# 1__schdoc.net
KiCad netlist of a schematic drawn in Altium Designer
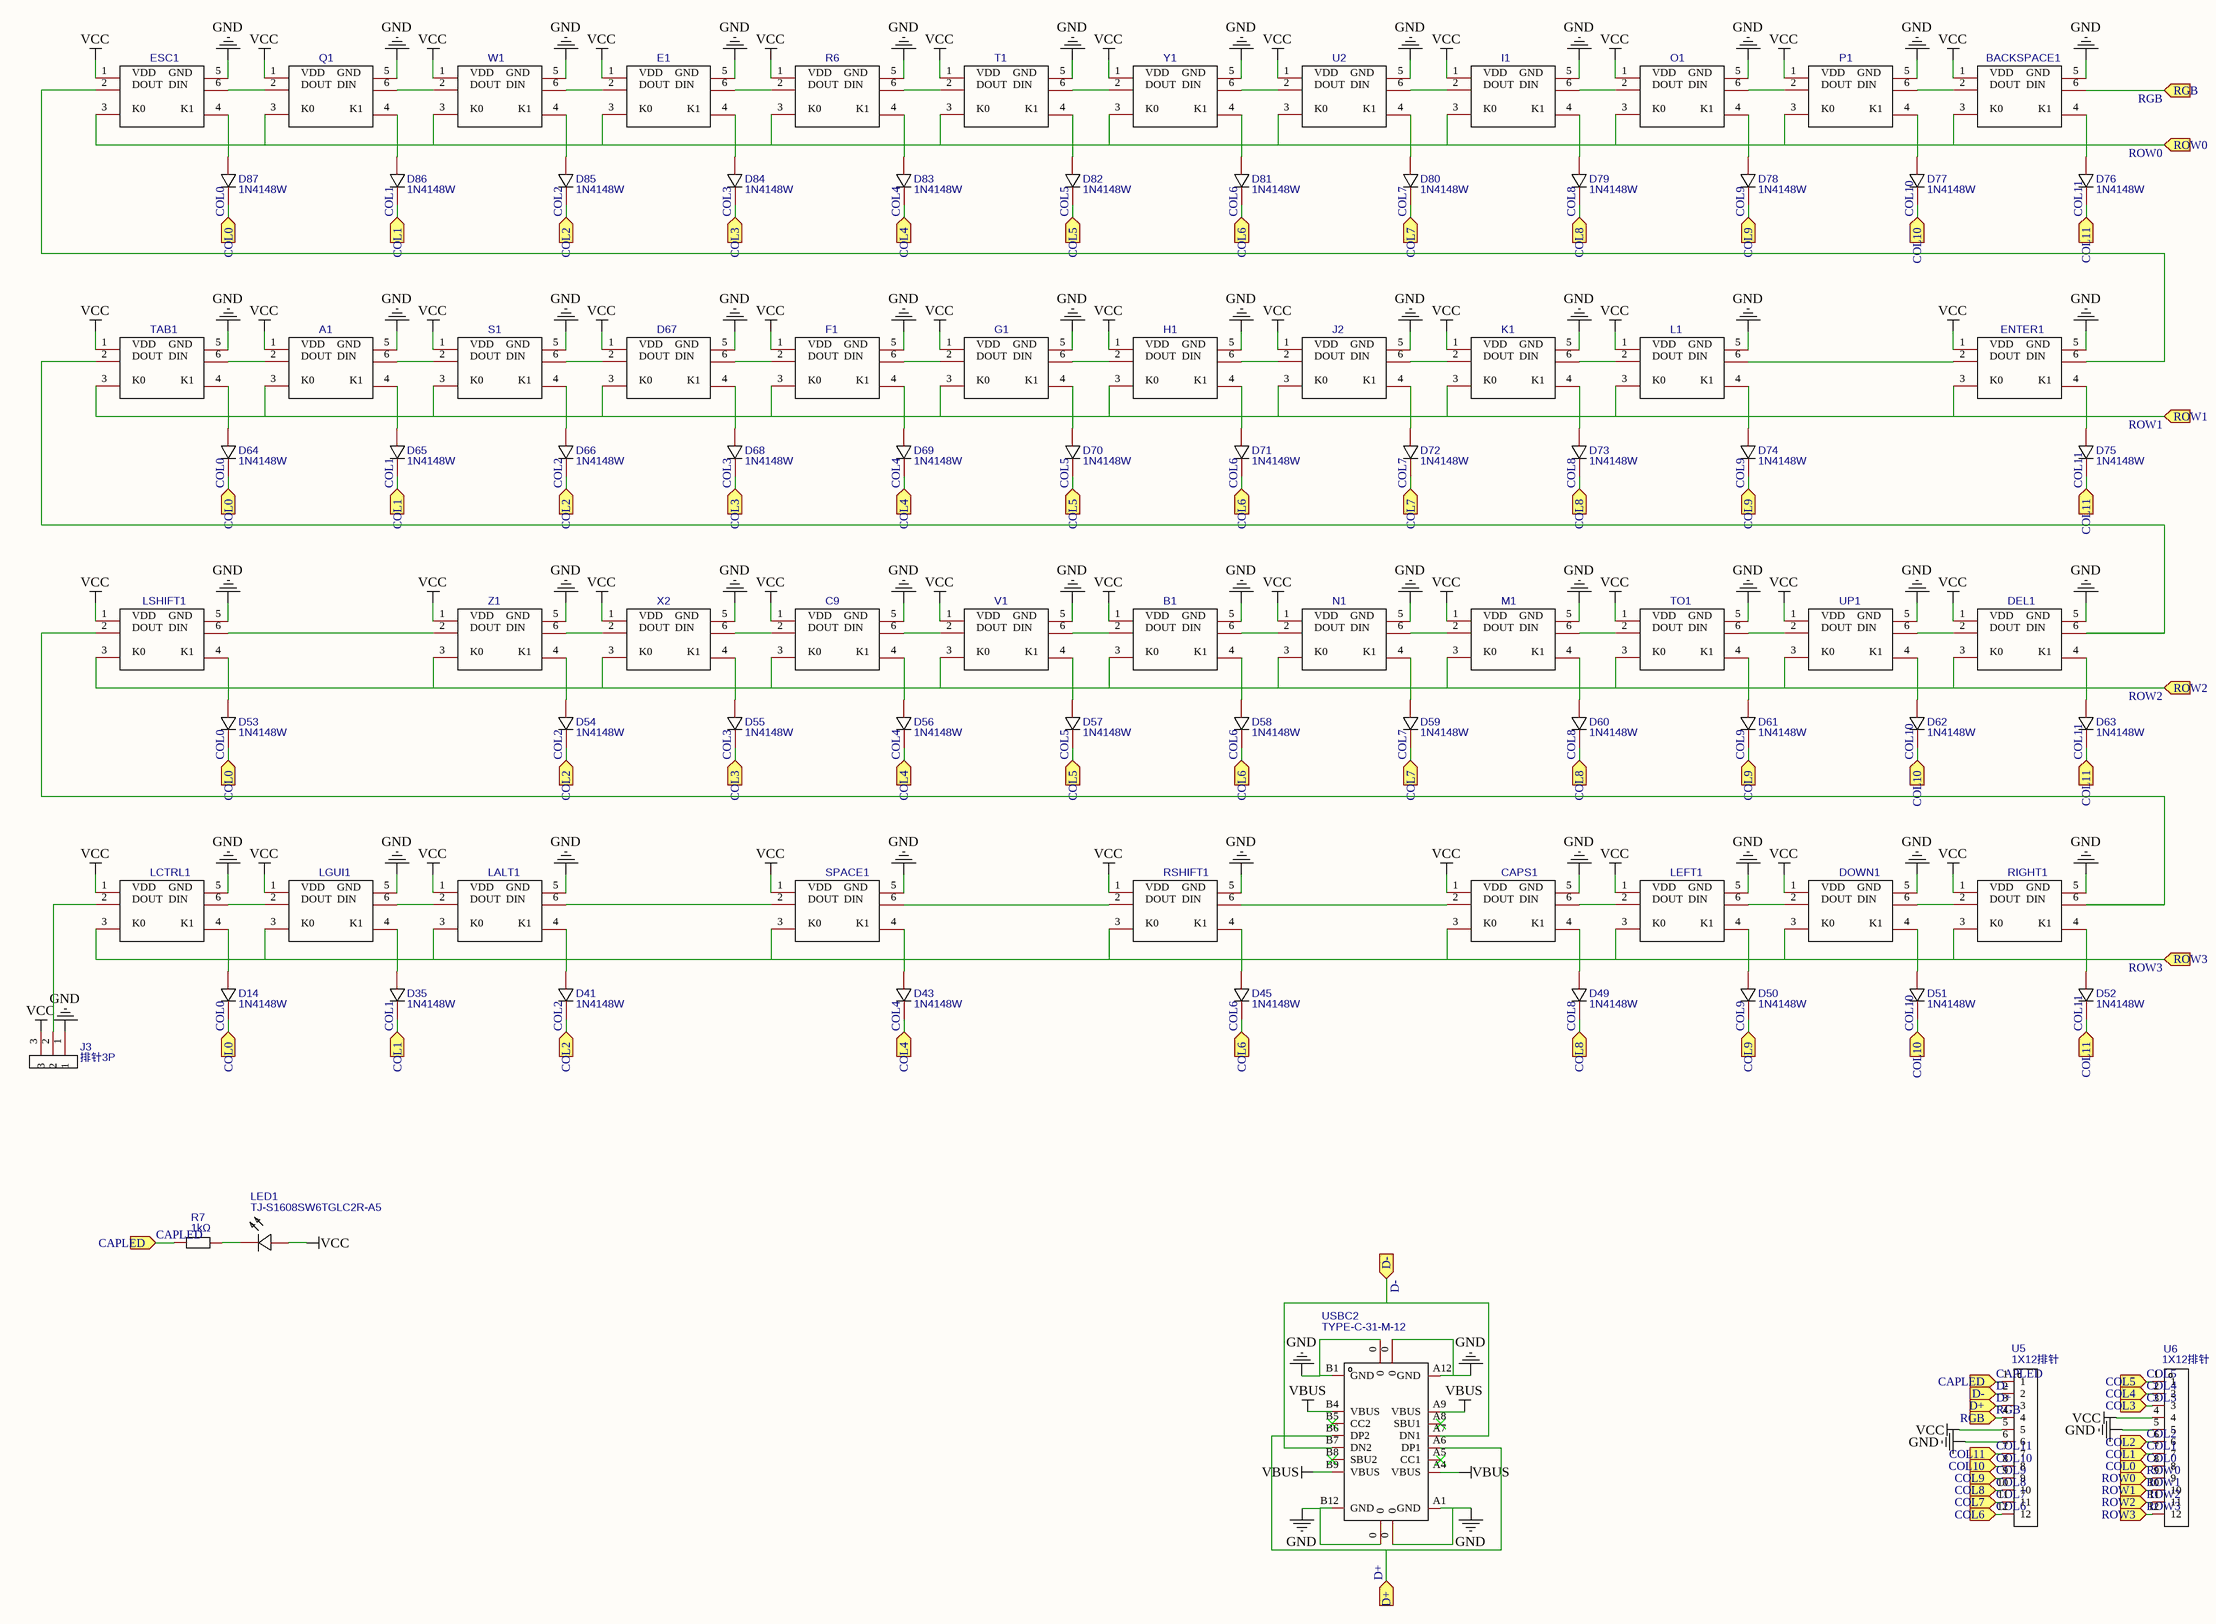
[diagram p0: 1_键盘矩阵.schdoc.schdoc]

(export (version "E")
  (design (tool "Eeschema 10.0.6"))
  (components
    (comp (ref "A1") (value "凯华轴座+3528反贴灯") (libsource (lib "altium-import") (part "root_0_凯华轴座+3528反贴灯_")))
    (comp (ref "B1") (value "凯华轴座+3528反贴灯") (libsource (lib "altium-import") (part "root_0_凯华轴座+3528反贴灯_")))
    (comp (ref "BACKSPACE1")
      (value "凯华轴座+3528反贴灯")
      (libsource (lib "altium-import") (part "root_0_凯华轴座+3528反贴灯_"))
    )
    (comp (ref "C9") (value "凯华轴座+3528反贴灯") (libsource (lib "altium-import") (part "root_0_凯华轴座+3528反贴灯_")))
    (comp (ref "CAPS1")
      (value "凯华轴座+3528反贴灯")
      (libsource (lib "altium-import") (part "root_0_凯华轴座+3528反贴灯_"))
    )
    (comp (ref "D14")
      (value "1N4148W")
      (fields (field (name "NAME") "1N4148W") (field (name "MANUFACTURER") "HT"))
      (libsource (lib "altium-import") (part "root_1_1N4148W_"))
    )
    (comp (ref "D35")
      (value "1N4148W")
      (fields (field (name "NAME") "1N4148W") (field (name "MANUFACTURER") "HT"))
      (libsource (lib "altium-import") (part "root_1_1N4148W_"))
    )
    (comp (ref "D41")
      (value "1N4148W")
      (fields (field (name "NAME") "1N4148W") (field (name "MANUFACTURER") "HT"))
      (libsource (lib "altium-import") (part "root_1_1N4148W_"))
    )
    (comp (ref "D43")
      (value "1N4148W")
      (fields (field (name "NAME") "1N4148W") (field (name "MANUFACTURER") "HT"))
      (libsource (lib "altium-import") (part "root_1_1N4148W_"))
    )
    (comp (ref "D45")
      (value "1N4148W")
      (fields (field (name "NAME") "1N4148W") (field (name "MANUFACTURER") "HT"))
      (libsource (lib "altium-import") (part "root_1_1N4148W_"))
    )
    (comp (ref "D49")
      (value "1N4148W")
      (fields (field (name "NAME") "1N4148W") (field (name "MANUFACTURER") "HT"))
      (libsource (lib "altium-import") (part "root_1_1N4148W_"))
    )
    (comp (ref "D50")
      (value "1N4148W")
      (fields (field (name "NAME") "1N4148W") (field (name "MANUFACTURER") "HT"))
      (libsource (lib "altium-import") (part "root_1_1N4148W_"))
    )
    (comp (ref "D51")
      (value "1N4148W")
      (fields (field (name "NAME") "1N4148W") (field (name "MANUFACTURER") "HT"))
      (libsource (lib "altium-import") (part "root_1_1N4148W_"))
    )
    (comp (ref "D52")
      (value "1N4148W")
      (fields (field (name "NAME") "1N4148W") (field (name "MANUFACTURER") "HT"))
      (libsource (lib "altium-import") (part "root_1_1N4148W_"))
    )
    (comp (ref "D53")
      (value "1N4148W")
      (fields (field (name "NAME") "1N4148W") (field (name "MANUFACTURER") "HT"))
      (libsource (lib "altium-import") (part "root_1_1N4148W_"))
    )
    (comp (ref "D54")
      (value "1N4148W")
      (fields (field (name "NAME") "1N4148W") (field (name "MANUFACTURER") "HT"))
      (libsource (lib "altium-import") (part "root_1_1N4148W_"))
    )
    (comp (ref "D55")
      (value "1N4148W")
      (fields (field (name "NAME") "1N4148W") (field (name "MANUFACTURER") "HT"))
      (libsource (lib "altium-import") (part "root_1_1N4148W_"))
    )
    (comp (ref "D56")
      (value "1N4148W")
      (fields (field (name "NAME") "1N4148W") (field (name "MANUFACTURER") "HT"))
      (libsource (lib "altium-import") (part "root_1_1N4148W_"))
    )
    (comp (ref "D57")
      (value "1N4148W")
      (fields (field (name "NAME") "1N4148W") (field (name "MANUFACTURER") "HT"))
      (libsource (lib "altium-import") (part "root_1_1N4148W_"))
    )
    (comp (ref "D58")
      (value "1N4148W")
      (fields (field (name "NAME") "1N4148W") (field (name "MANUFACTURER") "HT"))
      (libsource (lib "altium-import") (part "root_1_1N4148W_"))
    )
    (comp (ref "D59")
      (value "1N4148W")
      (fields (field (name "NAME") "1N4148W") (field (name "MANUFACTURER") "HT"))
      (libsource (lib "altium-import") (part "root_1_1N4148W_"))
    )
    (comp (ref "D60")
      (value "1N4148W")
      (fields (field (name "NAME") "1N4148W") (field (name "MANUFACTURER") "HT"))
      (libsource (lib "altium-import") (part "root_1_1N4148W_"))
    )
    (comp (ref "D61")
      (value "1N4148W")
      (fields (field (name "NAME") "1N4148W") (field (name "MANUFACTURER") "HT"))
      (libsource (lib "altium-import") (part "root_1_1N4148W_"))
    )
    (comp (ref "D62")
      (value "1N4148W")
      (fields (field (name "NAME") "1N4148W") (field (name "MANUFACTURER") "HT"))
      (libsource (lib "altium-import") (part "root_1_1N4148W_"))
    )
    (comp (ref "D63")
      (value "1N4148W")
      (fields (field (name "NAME") "1N4148W") (field (name "MANUFACTURER") "HT"))
      (libsource (lib "altium-import") (part "root_1_1N4148W_"))
    )
    (comp (ref "D64")
      (value "1N4148W")
      (fields (field (name "NAME") "1N4148W") (field (name "MANUFACTURER") "HT"))
      (libsource (lib "altium-import") (part "root_1_1N4148W_"))
    )
    (comp (ref "D65")
      (value "1N4148W")
      (fields (field (name "NAME") "1N4148W") (field (name "MANUFACTURER") "HT"))
      (libsource (lib "altium-import") (part "root_1_1N4148W_"))
    )
    (comp (ref "D66")
      (value "1N4148W")
      (fields (field (name "NAME") "1N4148W") (field (name "MANUFACTURER") "HT"))
      (libsource (lib "altium-import") (part "root_1_1N4148W_"))
    )
    (comp (ref "D67") (value "凯华轴座+3528反贴灯") (libsource (lib "altium-import") (part "root_0_凯华轴座+3528反贴灯_")))
    (comp (ref "D68")
      (value "1N4148W")
      (fields (field (name "NAME") "1N4148W") (field (name "MANUFACTURER") "HT"))
      (libsource (lib "altium-import") (part "root_1_1N4148W_"))
    )
    (comp (ref "D69")
      (value "1N4148W")
      (fields (field (name "NAME") "1N4148W") (field (name "MANUFACTURER") "HT"))
      (libsource (lib "altium-import") (part "root_1_1N4148W_"))
    )
    (comp (ref "D70")
      (value "1N4148W")
      (fields (field (name "NAME") "1N4148W") (field (name "MANUFACTURER") "HT"))
      (libsource (lib "altium-import") (part "root_1_1N4148W_"))
    )
    (comp (ref "D71")
      (value "1N4148W")
      (fields (field (name "NAME") "1N4148W") (field (name "MANUFACTURER") "HT"))
      (libsource (lib "altium-import") (part "root_1_1N4148W_"))
    )
    (comp (ref "D72")
      (value "1N4148W")
      (fields (field (name "NAME") "1N4148W") (field (name "MANUFACTURER") "HT"))
      (libsource (lib "altium-import") (part "root_1_1N4148W_"))
    )
    (comp (ref "D73")
      (value "1N4148W")
      (fields (field (name "NAME") "1N4148W") (field (name "MANUFACTURER") "HT"))
      (libsource (lib "altium-import") (part "root_1_1N4148W_"))
    )
    (comp (ref "D74")
      (value "1N4148W")
      (fields (field (name "NAME") "1N4148W") (field (name "MANUFACTURER") "HT"))
      (libsource (lib "altium-import") (part "root_1_1N4148W_"))
    )
    (comp (ref "D75")
      (value "1N4148W")
      (fields (field (name "NAME") "1N4148W") (field (name "MANUFACTURER") "HT"))
      (libsource (lib "altium-import") (part "root_1_1N4148W_"))
    )
    (comp (ref "D76")
      (value "1N4148W")
      (fields (field (name "NAME") "1N4148W") (field (name "MANUFACTURER") "HT"))
      (libsource (lib "altium-import") (part "root_1_1N4148W_"))
    )
    (comp (ref "D77")
      (value "1N4148W")
      (fields (field (name "NAME") "1N4148W") (field (name "MANUFACTURER") "HT"))
      (libsource (lib "altium-import") (part "root_1_1N4148W_"))
    )
    (comp (ref "D78")
      (value "1N4148W")
      (fields (field (name "NAME") "1N4148W") (field (name "MANUFACTURER") "HT"))
      (libsource (lib "altium-import") (part "root_1_1N4148W_"))
    )
    (comp (ref "D79")
      (value "1N4148W")
      (fields (field (name "NAME") "1N4148W") (field (name "MANUFACTURER") "HT"))
      (libsource (lib "altium-import") (part "root_1_1N4148W_"))
    )
    (comp (ref "D80")
      (value "1N4148W")
      (fields (field (name "NAME") "1N4148W") (field (name "MANUFACTURER") "HT"))
      (libsource (lib "altium-import") (part "root_1_1N4148W_"))
    )
    (comp (ref "D81")
      (value "1N4148W")
      (fields (field (name "NAME") "1N4148W") (field (name "MANUFACTURER") "HT"))
      (libsource (lib "altium-import") (part "root_1_1N4148W_"))
    )
    (comp (ref "D82")
      (value "1N4148W")
      (fields (field (name "NAME") "1N4148W") (field (name "MANUFACTURER") "HT"))
      (libsource (lib "altium-import") (part "root_1_1N4148W_"))
    )
    (comp (ref "D83")
      (value "1N4148W")
      (fields (field (name "NAME") "1N4148W") (field (name "MANUFACTURER") "HT"))
      (libsource (lib "altium-import") (part "root_1_1N4148W_"))
    )
    (comp (ref "D84")
      (value "1N4148W")
      (fields (field (name "NAME") "1N4148W") (field (name "MANUFACTURER") "HT"))
      (libsource (lib "altium-import") (part "root_1_1N4148W_"))
    )
    (comp (ref "D85")
      (value "1N4148W")
      (fields (field (name "NAME") "1N4148W") (field (name "MANUFACTURER") "HT"))
      (libsource (lib "altium-import") (part "root_1_1N4148W_"))
    )
    (comp (ref "D86")
      (value "1N4148W")
      (fields (field (name "NAME") "1N4148W") (field (name "MANUFACTURER") "HT"))
      (libsource (lib "altium-import") (part "root_1_1N4148W_"))
    )
    (comp (ref "D87")
      (value "1N4148W")
      (fields (field (name "NAME") "1N4148W") (field (name "MANUFACTURER") "HT"))
      (libsource (lib "altium-import") (part "root_1_1N4148W_"))
    )
    (comp (ref "DEL1") (value "凯华轴座+3528反贴灯") (libsource (lib "altium-import") (part "root_0_凯华轴座+3528反贴灯_")))
    (comp (ref "DOWN1")
      (value "凯华轴座+3528反贴灯")
      (libsource (lib "altium-import") (part "root_0_凯华轴座+3528反贴灯_"))
    )
    (comp (ref "E1") (value "凯华轴座+3528反贴灯") (libsource (lib "altium-import") (part "root_0_凯华轴座+3528反贴灯_")))
    (comp (ref "ENTER1")
      (value "凯华轴座+3528反贴灯")
      (libsource (lib "altium-import") (part "root_0_凯华轴座+3528反贴灯_"))
    )
    (comp (ref "ESC1") (value "凯华轴座+3528反贴灯") (libsource (lib "altium-import") (part "root_0_凯华轴座+3528反贴灯_")))
    (comp (ref "F1") (value "凯华轴座+3528反贴灯") (libsource (lib "altium-import") (part "root_0_凯华轴座+3528反贴灯_")))
    (comp (ref "G1") (value "凯华轴座+3528反贴灯") (libsource (lib "altium-import") (part "root_0_凯华轴座+3528反贴灯_")))
    (comp (ref "H1") (value "凯华轴座+3528反贴灯") (libsource (lib "altium-import") (part "root_0_凯华轴座+3528反贴灯_")))
    (comp (ref "I1") (value "凯华轴座+3528反贴灯") (libsource (lib "altium-import") (part "root_0_凯华轴座+3528反贴灯_")))
    (comp (ref "J2") (value "凯华轴座+3528反贴灯") (libsource (lib "altium-import") (part "root_0_凯华轴座+3528反贴灯_")))
    (comp (ref "J3")
      (value "排针3P")
      (fields (field (name "NAME") "排针3P"))
      (libsource (lib "altium-import") (part "root_3_排针3P_"))
    )
    (comp (ref "K1") (value "凯华轴座+3528反贴灯") (libsource (lib "altium-import") (part "root_0_凯华轴座+3528反贴灯_")))
    (comp (ref "L1") (value "凯华轴座+3528反贴灯") (libsource (lib "altium-import") (part "root_0_凯华轴座+3528反贴灯_")))
    (comp (ref "LALT1")
      (value "凯华轴座+3528反贴灯")
      (libsource (lib "altium-import") (part "root_0_凯华轴座+3528反贴灯_"))
    )
    (comp (ref "LCTRL1")
      (value "凯华轴座+3528反贴灯")
      (libsource (lib "altium-import") (part "root_0_凯华轴座+3528反贴灯_"))
    )
    (comp (ref "LED1")
      (value "TJ-S1608SW6TGLC2R-A5")
      (fields (field (name "NAME") "TJ-S1608SW6TGLC2R-A5") (field (name "MANUFACTURER") "TOGIALED"))
      (libsource (lib "altium-import") (part "root_0_TJ-S1608SW6TGLC2R-A5_"))
    )
    (comp (ref "LEFT1")
      (value "凯华轴座+3528反贴灯")
      (libsource (lib "altium-import") (part "root_0_凯华轴座+3528反贴灯_"))
    )
    (comp (ref "LGUI1")
      (value "凯华轴座+3528反贴灯")
      (libsource (lib "altium-import") (part "root_0_凯华轴座+3528反贴灯_"))
    )
    (comp (ref "LSHIFT1")
      (value "凯华轴座+3528反贴灯")
      (libsource (lib "altium-import") (part "root_0_凯华轴座+3528反贴灯_"))
    )
    (comp (ref "M1") (value "凯华轴座+3528反贴灯") (libsource (lib "altium-import") (part "root_0_凯华轴座+3528反贴灯_")))
    (comp (ref "N1") (value "凯华轴座+3528反贴灯") (libsource (lib "altium-import") (part "root_0_凯华轴座+3528反贴灯_")))
    (comp (ref "O1") (value "凯华轴座+3528反贴灯") (libsource (lib "altium-import") (part "root_0_凯华轴座+3528反贴灯_")))
    (comp (ref "P1") (value "凯华轴座+3528反贴灯") (libsource (lib "altium-import") (part "root_0_凯华轴座+3528反贴灯_")))
    (comp (ref "Q1") (value "凯华轴座+3528反贴灯") (libsource (lib "altium-import") (part "root_0_凯华轴座+3528反贴灯_")))
    (comp (ref "R6") (value "凯华轴座+3528反贴灯") (libsource (lib "altium-import") (part "root_0_凯华轴座+3528反贴灯_")))
    (comp (ref "R7")
      (value "1kΩ")
      (fields
        (field (name "NAME") "1kΩ")
        (field (name "MANUFACTURER") "ResistorToday")
        (field (name "MANUFACTURER PART") "ETCR0603F1K00K9")
      )
      (libsource (lib "altium-import") (part "root_0_ETCR0603F1K00K9_"))
    )
    (comp (ref "RIGHT1")
      (value "凯华轴座+3528反贴灯")
      (libsource (lib "altium-import") (part "root_0_凯华轴座+3528反贴灯_"))
    )
    (comp (ref "RSHIFT1")
      (value "凯华轴座+3528反贴灯")
      (libsource (lib "altium-import") (part "root_0_凯华轴座+3528反贴灯_"))
    )
    (comp (ref "S1") (value "凯华轴座+3528反贴灯") (libsource (lib "altium-import") (part "root_0_凯华轴座+3528反贴灯_")))
    (comp (ref "SPACE1")
      (value "凯华轴座+3528反贴灯")
      (libsource (lib "altium-import") (part "root_0_凯华轴座+3528反贴灯_"))
    )
    (comp (ref "T1") (value "凯华轴座+3528反贴灯") (libsource (lib "altium-import") (part "root_0_凯华轴座+3528反贴灯_")))
    (comp (ref "TAB1") (value "凯华轴座+3528反贴灯") (libsource (lib "altium-import") (part "root_0_凯华轴座+3528反贴灯_")))
    (comp (ref "TO1") (value "凯华轴座+3528反贴灯") (libsource (lib "altium-import") (part "root_0_凯华轴座+3528反贴灯_")))
    (comp (ref "U2") (value "凯华轴座+3528反贴灯") (libsource (lib "altium-import") (part "root_0_凯华轴座+3528反贴灯_")))
    (comp (ref "U5")
      (value "1X12排针")
      (fields (field (name "NAME") "1X12排针"))
      (libsource (lib "altium-import") (part "root_0_1X12排针_"))
    )
    (comp (ref "U6")
      (value "1X12排针")
      (fields (field (name "NAME") "1X12排针"))
      (libsource (lib "altium-import") (part "root_0_1X12排针_"))
    )
    (comp (ref "UP1") (value "凯华轴座+3528反贴灯") (libsource (lib "altium-import") (part "root_0_凯华轴座+3528反贴灯_")))
    (comp (ref "USBC2")
      (value "TYPE-C-31-M-12")
      (fields
        (field (name "NAME") "TYPE-C-31-M-12")
        (field (name "MANUFACTURER") "RectangularConnectors-Contacts")
      )
      (libsource (lib "altium-import") (part "root_0_TYPE-C-31-M-12_"))
    )
    (comp (ref "V1") (value "凯华轴座+3528反贴灯") (libsource (lib "altium-import") (part "root_0_凯华轴座+3528反贴灯_")))
    (comp (ref "W1") (value "凯华轴座+3528反贴灯") (libsource (lib "altium-import") (part "root_0_凯华轴座+3528反贴灯_")))
    (comp (ref "X2") (value "凯华轴座+3528反贴灯") (libsource (lib "altium-import") (part "root_0_凯华轴座+3528反贴灯_")))
    (comp (ref "Y1") (value "凯华轴座+3528反贴灯") (libsource (lib "altium-import") (part "root_0_凯华轴座+3528反贴灯_")))
    (comp (ref "Z1") (value "凯华轴座+3528反贴灯") (libsource (lib "altium-import") (part "root_0_凯华轴座+3528反贴灯_")))
  )
  (nets
    (net (code "1") (name "/CAPLED") (class "Default")
      (node (ref "R7") (pin "1") (pinfunction "1_1") (pintype "passive"))
      (node (ref "U5") (pin "1") (pinfunction "1_1") (pintype "passive"))
    )
    (net (code "2") (name "/COL0") (class "Default")
      (node (ref "D14") (pin "1") (pinfunction "K_1") (pintype "passive"))
      (node (ref "D53") (pin "1") (pinfunction "K_1") (pintype "passive"))
      (node (ref "D64") (pin "1") (pinfunction "K_1") (pintype "passive"))
      (node (ref "D87") (pin "1") (pinfunction "K_1") (pintype "passive"))
      (node (ref "U6") (pin "8") (pinfunction "8_8") (pintype "passive"))
    )
    (net (code "3") (name "/COL1") (class "Default")
      (node (ref "D35") (pin "1") (pinfunction "K_1") (pintype "passive"))
      (node (ref "D65") (pin "1") (pinfunction "K_1") (pintype "passive"))
      (node (ref "D86") (pin "1") (pinfunction "K_1") (pintype "passive"))
      (node (ref "U6") (pin "7") (pinfunction "7_7") (pintype "passive"))
    )
    (net (code "4") (name "/COL2") (class "Default")
      (node (ref "D41") (pin "1") (pinfunction "K_1") (pintype "passive"))
      (node (ref "D54") (pin "1") (pinfunction "K_1") (pintype "passive"))
      (node (ref "D66") (pin "1") (pinfunction "K_1") (pintype "passive"))
      (node (ref "D85") (pin "1") (pinfunction "K_1") (pintype "passive"))
      (node (ref "U6") (pin "6") (pinfunction "6_6") (pintype "passive"))
    )
    (net (code "5") (name "/COL3") (class "Default")
      (node (ref "D55") (pin "1") (pinfunction "K_1") (pintype "passive"))
      (node (ref "D68") (pin "1") (pinfunction "K_1") (pintype "passive"))
      (node (ref "D84") (pin "1") (pinfunction "K_1") (pintype "passive"))
      (node (ref "U6") (pin "3") (pinfunction "3_3") (pintype "passive"))
    )
    (net (code "6") (name "/COL4") (class "Default")
      (node (ref "D43") (pin "1") (pinfunction "K_1") (pintype "passive"))
      (node (ref "D56") (pin "1") (pinfunction "K_1") (pintype "passive"))
      (node (ref "D69") (pin "1") (pinfunction "K_1") (pintype "passive"))
      (node (ref "D83") (pin "1") (pinfunction "K_1") (pintype "passive"))
      (node (ref "U6") (pin "2") (pinfunction "2_2") (pintype "passive"))
    )
    (net (code "7") (name "/COL5") (class "Default")
      (node (ref "D57") (pin "1") (pinfunction "K_1") (pintype "passive"))
      (node (ref "D70") (pin "1") (pinfunction "K_1") (pintype "passive"))
      (node (ref "D82") (pin "1") (pinfunction "K_1") (pintype "passive"))
      (node (ref "U6") (pin "1") (pinfunction "1_1") (pintype "passive"))
    )
    (net (code "8") (name "/COL6") (class "Default")
      (node (ref "D45") (pin "1") (pinfunction "K_1") (pintype "passive"))
      (node (ref "D58") (pin "1") (pinfunction "K_1") (pintype "passive"))
      (node (ref "D71") (pin "1") (pinfunction "K_1") (pintype "passive"))
      (node (ref "D81") (pin "1") (pinfunction "K_1") (pintype "passive"))
      (node (ref "U5") (pin "12") (pinfunction "12_12") (pintype "passive"))
    )
    (net (code "9") (name "/COL7") (class "Default")
      (node (ref "D59") (pin "1") (pinfunction "K_1") (pintype "passive"))
      (node (ref "D72") (pin "1") (pinfunction "K_1") (pintype "passive"))
      (node (ref "D80") (pin "1") (pinfunction "K_1") (pintype "passive"))
      (node (ref "U5") (pin "11") (pinfunction "11_11") (pintype "passive"))
    )
    (net (code "10") (name "/COL8") (class "Default")
      (node (ref "D49") (pin "1") (pinfunction "K_1") (pintype "passive"))
      (node (ref "D60") (pin "1") (pinfunction "K_1") (pintype "passive"))
      (node (ref "D73") (pin "1") (pinfunction "K_1") (pintype "passive"))
      (node (ref "D79") (pin "1") (pinfunction "K_1") (pintype "passive"))
      (node (ref "U5") (pin "10") (pinfunction "10_10") (pintype "passive"))
    )
    (net (code "11") (name "/COL9") (class "Default")
      (node (ref "D50") (pin "1") (pinfunction "K_1") (pintype "passive"))
      (node (ref "D61") (pin "1") (pinfunction "K_1") (pintype "passive"))
      (node (ref "D74") (pin "1") (pinfunction "K_1") (pintype "passive"))
      (node (ref "D78") (pin "1") (pinfunction "K_1") (pintype "passive"))
      (node (ref "U5") (pin "9") (pinfunction "9_9") (pintype "passive"))
    )
    (net (code "12") (name "/COL10") (class "Default")
      (node (ref "D51") (pin "1") (pinfunction "K_1") (pintype "passive"))
      (node (ref "D62") (pin "1") (pinfunction "K_1") (pintype "passive"))
      (node (ref "D77") (pin "1") (pinfunction "K_1") (pintype "passive"))
      (node (ref "U5") (pin "8") (pinfunction "8_8") (pintype "passive"))
    )
    (net (code "13") (name "/COL11") (class "Default")
      (node (ref "D52") (pin "1") (pinfunction "K_1") (pintype "passive"))
      (node (ref "D63") (pin "1") (pinfunction "K_1") (pintype "passive"))
      (node (ref "D75") (pin "1") (pinfunction "K_1") (pintype "passive"))
      (node (ref "D76") (pin "1") (pinfunction "K_1") (pintype "passive"))
      (node (ref "U5") (pin "7") (pinfunction "7_7") (pintype "passive"))
    )
    (net (code "14") (name "/D+") (class "Default")
      (node (ref "U5") (pin "3") (pinfunction "3_3") (pintype "passive"))
      (node (ref "USBC2") (pin "A6") (pinfunction "DP1_A6") (pintype "passive"))
      (node (ref "USBC2") (pin "B6") (pinfunction "DP2_B6") (pintype "passive"))
    )
    (net (code "15") (name "/D-") (class "Default")
      (node (ref "U5") (pin "2") (pinfunction "2_2") (pintype "passive"))
      (node (ref "USBC2") (pin "A7") (pinfunction "DN1_A7") (pintype "passive"))
      (node (ref "USBC2") (pin "B7") (pinfunction "DN2_B7") (pintype "passive"))
    )
    (net (code "16") (name "/RGB") (class "Default")
      (node (ref "BACKSPACE1") (pin "6") (pinfunction "6_6") (pintype "passive"))
      (node (ref "U5") (pin "4") (pinfunction "4_4") (pintype "passive"))
    )
    (net (code "17") (name "/ROW0") (class "Default")
      (node (ref "BACKSPACE1") (pin "3") (pinfunction "3_3") (pintype "passive"))
      (node (ref "E1") (pin "3") (pinfunction "3_3") (pintype "passive"))
      (node (ref "ESC1") (pin "3") (pinfunction "3_3") (pintype "passive"))
      (node (ref "I1") (pin "3") (pinfunction "3_3") (pintype "passive"))
      (node (ref "O1") (pin "3") (pinfunction "3_3") (pintype "passive"))
      (node (ref "P1") (pin "3") (pinfunction "3_3") (pintype "passive"))
      (node (ref "Q1") (pin "3") (pinfunction "3_3") (pintype "passive"))
      (node (ref "R6") (pin "3") (pinfunction "3_3") (pintype "passive"))
      (node (ref "T1") (pin "3") (pinfunction "3_3") (pintype "passive"))
      (node (ref "U2") (pin "3") (pinfunction "3_3") (pintype "passive"))
      (node (ref "U6") (pin "9") (pinfunction "9_9") (pintype "passive"))
      (node (ref "W1") (pin "3") (pinfunction "3_3") (pintype "passive"))
      (node (ref "Y1") (pin "3") (pinfunction "3_3") (pintype "passive"))
    )
    (net (code "18") (name "/ROW1") (class "Default")
      (node (ref "A1") (pin "3") (pinfunction "3_3") (pintype "passive"))
      (node (ref "D67") (pin "3") (pinfunction "3_3") (pintype "passive"))
      (node (ref "ENTER1") (pin "3") (pinfunction "3_3") (pintype "passive"))
      (node (ref "F1") (pin "3") (pinfunction "3_3") (pintype "passive"))
      (node (ref "G1") (pin "3") (pinfunction "3_3") (pintype "passive"))
      (node (ref "H1") (pin "3") (pinfunction "3_3") (pintype "passive"))
      (node (ref "J2") (pin "3") (pinfunction "3_3") (pintype "passive"))
      (node (ref "K1") (pin "3") (pinfunction "3_3") (pintype "passive"))
      (node (ref "L1") (pin "3") (pinfunction "3_3") (pintype "passive"))
      (node (ref "S1") (pin "3") (pinfunction "3_3") (pintype "passive"))
      (node (ref "TAB1") (pin "3") (pinfunction "3_3") (pintype "passive"))
      (node (ref "U6") (pin "10") (pinfunction "10_10") (pintype "passive"))
    )
    (net (code "19") (name "/ROW2") (class "Default")
      (node (ref "B1") (pin "3") (pinfunction "3_3") (pintype "passive"))
      (node (ref "C9") (pin "3") (pinfunction "3_3") (pintype "passive"))
      (node (ref "DEL1") (pin "3") (pinfunction "3_3") (pintype "passive"))
      (node (ref "LSHIFT1") (pin "3") (pinfunction "3_3") (pintype "passive"))
      (node (ref "M1") (pin "3") (pinfunction "3_3") (pintype "passive"))
      (node (ref "N1") (pin "3") (pinfunction "3_3") (pintype "passive"))
      (node (ref "TO1") (pin "3") (pinfunction "3_3") (pintype "passive"))
      (node (ref "U6") (pin "11") (pinfunction "11_11") (pintype "passive"))
      (node (ref "UP1") (pin "3") (pinfunction "3_3") (pintype "passive"))
      (node (ref "V1") (pin "3") (pinfunction "3_3") (pintype "passive"))
      (node (ref "X2") (pin "3") (pinfunction "3_3") (pintype "passive"))
      (node (ref "Z1") (pin "3") (pinfunction "3_3") (pintype "passive"))
    )
    (net (code "20") (name "/ROW3") (class "Default")
      (node (ref "CAPS1") (pin "3") (pinfunction "3_3") (pintype "passive"))
      (node (ref "DOWN1") (pin "3") (pinfunction "3_3") (pintype "passive"))
      (node (ref "LALT1") (pin "3") (pinfunction "3_3") (pintype "passive"))
      (node (ref "LCTRL1") (pin "3") (pinfunction "3_3") (pintype "passive"))
      (node (ref "LEFT1") (pin "3") (pinfunction "3_3") (pintype "passive"))
      (node (ref "LGUI1") (pin "3") (pinfunction "3_3") (pintype "passive"))
      (node (ref "RIGHT1") (pin "3") (pinfunction "3_3") (pintype "passive"))
      (node (ref "RSHIFT1") (pin "3") (pinfunction "3_3") (pintype "passive"))
      (node (ref "SPACE1") (pin "3") (pinfunction "3_3") (pintype "passive"))
      (node (ref "U6") (pin "12") (pinfunction "12_12") (pintype "passive"))
    )
    (net (code "21") (name "GND") (class "Default")
      (node (ref "A1") (pin "5") (pinfunction "5_5") (pintype "passive"))
      (node (ref "B1") (pin "5") (pinfunction "5_5") (pintype "passive"))
      (node (ref "BACKSPACE1") (pin "5") (pinfunction "5_5") (pintype "passive"))
      (node (ref "C9") (pin "5") (pinfunction "5_5") (pintype "passive"))
      (node (ref "CAPS1") (pin "5") (pinfunction "5_5") (pintype "passive"))
      (node (ref "D67") (pin "5") (pinfunction "5_5") (pintype "passive"))
      (node (ref "DEL1") (pin "5") (pinfunction "5_5") (pintype "passive"))
      (node (ref "DOWN1") (pin "5") (pinfunction "5_5") (pintype "passive"))
      (node (ref "E1") (pin "5") (pinfunction "5_5") (pintype "passive"))
      (node (ref "ENTER1") (pin "5") (pinfunction "5_5") (pintype "passive"))
      (node (ref "ESC1") (pin "5") (pinfunction "5_5") (pintype "passive"))
      (node (ref "F1") (pin "5") (pinfunction "5_5") (pintype "passive"))
      (node (ref "G1") (pin "5") (pinfunction "5_5") (pintype "passive"))
      (node (ref "H1") (pin "5") (pinfunction "5_5") (pintype "passive"))
      (node (ref "I1") (pin "5") (pinfunction "5_5") (pintype "passive"))
      (node (ref "J2") (pin "5") (pinfunction "5_5") (pintype "passive"))
      (node (ref "J3") (pin "1") (pinfunction "1_1") (pintype "passive"))
      (node (ref "K1") (pin "5") (pinfunction "5_5") (pintype "passive"))
      (node (ref "L1") (pin "5") (pinfunction "5_5") (pintype "passive"))
      (node (ref "LALT1") (pin "5") (pinfunction "5_5") (pintype "passive"))
      (node (ref "LCTRL1") (pin "5") (pinfunction "5_5") (pintype "passive"))
      (node (ref "LEFT1") (pin "5") (pinfunction "5_5") (pintype "passive"))
      (node (ref "LGUI1") (pin "5") (pinfunction "5_5") (pintype "passive"))
      (node (ref "LSHIFT1") (pin "5") (pinfunction "5_5") (pintype "passive"))
      (node (ref "M1") (pin "5") (pinfunction "5_5") (pintype "passive"))
      (node (ref "N1") (pin "5") (pinfunction "5_5") (pintype "passive"))
      (node (ref "O1") (pin "5") (pinfunction "5_5") (pintype "passive"))
      (node (ref "P1") (pin "5") (pinfunction "5_5") (pintype "passive"))
      (node (ref "Q1") (pin "5") (pinfunction "5_5") (pintype "passive"))
      (node (ref "R6") (pin "5") (pinfunction "5_5") (pintype "passive"))
      (node (ref "RIGHT1") (pin "5") (pinfunction "5_5") (pintype "passive"))
      (node (ref "RSHIFT1") (pin "5") (pinfunction "5_5") (pintype "passive"))
      (node (ref "S1") (pin "5") (pinfunction "5_5") (pintype "passive"))
      (node (ref "SPACE1") (pin "5") (pinfunction "5_5") (pintype "passive"))
      (node (ref "T1") (pin "5") (pinfunction "5_5") (pintype "passive"))
      (node (ref "TAB1") (pin "5") (pinfunction "5_5") (pintype "passive"))
      (node (ref "TO1") (pin "5") (pinfunction "5_5") (pintype "passive"))
      (node (ref "U2") (pin "5") (pinfunction "5_5") (pintype "passive"))
      (node (ref "U5") (pin "6") (pinfunction "6_6") (pintype "passive"))
      (node (ref "U6") (pin "5") (pinfunction "5_5") (pintype "passive"))
      (node (ref "UP1") (pin "5") (pinfunction "5_5") (pintype "passive"))
      (node (ref "USBC2") (pin "0") (pinfunction "0_0") (pintype "passive"))
      (node (ref "USBC2") (pin "A1") (pinfunction "GND_A1") (pintype "passive"))
      (node (ref "USBC2") (pin "A12") (pinfunction "GND_A12") (pintype "passive"))
      (node (ref "USBC2") (pin "B1") (pinfunction "GND_B1") (pintype "passive"))
      (node (ref "USBC2") (pin "B12") (pinfunction "GND_B12") (pintype "passive"))
      (node (ref "V1") (pin "5") (pinfunction "5_5") (pintype "passive"))
      (node (ref "W1") (pin "5") (pinfunction "5_5") (pintype "passive"))
      (node (ref "X2") (pin "5") (pinfunction "5_5") (pintype "passive"))
      (node (ref "Y1") (pin "5") (pinfunction "5_5") (pintype "passive"))
      (node (ref "Z1") (pin "5") (pinfunction "5_5") (pintype "passive"))
    )
    (net (code "22") (name "Net-(A1-Pad2)") (class "Default")
      (node (ref "A1") (pin "2") (pinfunction "2_2") (pintype "passive"))
      (node (ref "TAB1") (pin "6") (pinfunction "6_6") (pintype "passive"))
    )
    (net (code "23") (name "Net-(A1-Pad6)") (class "Default")
      (node (ref "A1") (pin "6") (pinfunction "6_6") (pintype "passive"))
      (node (ref "S1") (pin "2") (pinfunction "2_2") (pintype "passive"))
    )
    (net (code "24") (name "Net-(B1-Pad2)") (class "Default")
      (node (ref "B1") (pin "2") (pinfunction "2_2") (pintype "passive"))
      (node (ref "V1") (pin "6") (pinfunction "6_6") (pintype "passive"))
    )
    (net (code "25") (name "Net-(B1-Pad6)") (class "Default")
      (node (ref "B1") (pin "6") (pinfunction "6_6") (pintype "passive"))
      (node (ref "N1") (pin "2") (pinfunction "2_2") (pintype "passive"))
    )
    (net (code "26") (name "Net-(BACKSPACE1-Pad2)") (class "Default")
      (node (ref "BACKSPACE1") (pin "2") (pinfunction "2_2") (pintype "passive"))
      (node (ref "P1") (pin "6") (pinfunction "6_6") (pintype "passive"))
    )
    (net (code "27") (name "Net-(C9-Pad2)") (class "Default")
      (node (ref "C9") (pin "2") (pinfunction "2_2") (pintype "passive"))
      (node (ref "X2") (pin "6") (pinfunction "6_6") (pintype "passive"))
    )
    (net (code "28") (name "Net-(C9-Pad6)") (class "Default")
      (node (ref "C9") (pin "6") (pinfunction "6_6") (pintype "passive"))
      (node (ref "V1") (pin "2") (pinfunction "2_2") (pintype "passive"))
    )
    (net (code "29") (name "Net-(CAPS1-Pad2)") (class "Default")
      (node (ref "CAPS1") (pin "2") (pinfunction "2_2") (pintype "passive"))
      (node (ref "RSHIFT1") (pin "6") (pinfunction "6_6") (pintype "passive"))
    )
    (net (code "30") (name "Net-(CAPS1-Pad6)") (class "Default")
      (node (ref "CAPS1") (pin "6") (pinfunction "6_6") (pintype "passive"))
      (node (ref "LEFT1") (pin "2") (pinfunction "2_2") (pintype "passive"))
    )
    (net (code "31") (name "Net-(D14-A)") (class "Default")
      (node (ref "D14") (pin "2") (pinfunction "A_2") (pintype "passive"))
      (node (ref "LCTRL1") (pin "4") (pinfunction "4_4") (pintype "passive"))
    )
    (net (code "32") (name "Net-(D35-A)") (class "Default")
      (node (ref "D35") (pin "2") (pinfunction "A_2") (pintype "passive"))
      (node (ref "LGUI1") (pin "4") (pinfunction "4_4") (pintype "passive"))
    )
    (net (code "33") (name "Net-(D41-A)") (class "Default")
      (node (ref "D41") (pin "2") (pinfunction "A_2") (pintype "passive"))
      (node (ref "LALT1") (pin "4") (pinfunction "4_4") (pintype "passive"))
    )
    (net (code "34") (name "Net-(D43-A)") (class "Default")
      (node (ref "D43") (pin "2") (pinfunction "A_2") (pintype "passive"))
      (node (ref "SPACE1") (pin "4") (pinfunction "4_4") (pintype "passive"))
    )
    (net (code "35") (name "Net-(D45-A)") (class "Default")
      (node (ref "D45") (pin "2") (pinfunction "A_2") (pintype "passive"))
      (node (ref "RSHIFT1") (pin "4") (pinfunction "4_4") (pintype "passive"))
    )
    (net (code "36") (name "Net-(D49-A)") (class "Default")
      (node (ref "CAPS1") (pin "4") (pinfunction "4_4") (pintype "passive"))
      (node (ref "D49") (pin "2") (pinfunction "A_2") (pintype "passive"))
    )
    (net (code "37") (name "Net-(D50-A)") (class "Default")
      (node (ref "D50") (pin "2") (pinfunction "A_2") (pintype "passive"))
      (node (ref "LEFT1") (pin "4") (pinfunction "4_4") (pintype "passive"))
    )
    (net (code "38") (name "Net-(D51-A)") (class "Default")
      (node (ref "D51") (pin "2") (pinfunction "A_2") (pintype "passive"))
      (node (ref "DOWN1") (pin "4") (pinfunction "4_4") (pintype "passive"))
    )
    (net (code "39") (name "Net-(D52-A)") (class "Default")
      (node (ref "D52") (pin "2") (pinfunction "A_2") (pintype "passive"))
      (node (ref "RIGHT1") (pin "4") (pinfunction "4_4") (pintype "passive"))
    )
    (net (code "40") (name "Net-(D53-A)") (class "Default")
      (node (ref "D53") (pin "2") (pinfunction "A_2") (pintype "passive"))
      (node (ref "LSHIFT1") (pin "4") (pinfunction "4_4") (pintype "passive"))
    )
    (net (code "41") (name "Net-(D54-A)") (class "Default")
      (node (ref "D54") (pin "2") (pinfunction "A_2") (pintype "passive"))
      (node (ref "Z1") (pin "4") (pinfunction "4_4") (pintype "passive"))
    )
    (net (code "42") (name "Net-(D55-A)") (class "Default")
      (node (ref "D55") (pin "2") (pinfunction "A_2") (pintype "passive"))
      (node (ref "X2") (pin "4") (pinfunction "4_4") (pintype "passive"))
    )
    (net (code "43") (name "Net-(D56-A)") (class "Default")
      (node (ref "C9") (pin "4") (pinfunction "4_4") (pintype "passive"))
      (node (ref "D56") (pin "2") (pinfunction "A_2") (pintype "passive"))
    )
    (net (code "44") (name "Net-(D57-A)") (class "Default")
      (node (ref "D57") (pin "2") (pinfunction "A_2") (pintype "passive"))
      (node (ref "V1") (pin "4") (pinfunction "4_4") (pintype "passive"))
    )
    (net (code "45") (name "Net-(D58-A)") (class "Default")
      (node (ref "B1") (pin "4") (pinfunction "4_4") (pintype "passive"))
      (node (ref "D58") (pin "2") (pinfunction "A_2") (pintype "passive"))
    )
    (net (code "46") (name "Net-(D59-A)") (class "Default")
      (node (ref "D59") (pin "2") (pinfunction "A_2") (pintype "passive"))
      (node (ref "N1") (pin "4") (pinfunction "4_4") (pintype "passive"))
    )
    (net (code "47") (name "Net-(D60-A)") (class "Default")
      (node (ref "D60") (pin "2") (pinfunction "A_2") (pintype "passive"))
      (node (ref "M1") (pin "4") (pinfunction "4_4") (pintype "passive"))
    )
    (net (code "48") (name "Net-(D61-A)") (class "Default")
      (node (ref "D61") (pin "2") (pinfunction "A_2") (pintype "passive"))
      (node (ref "TO1") (pin "4") (pinfunction "4_4") (pintype "passive"))
    )
    (net (code "49") (name "Net-(D62-A)") (class "Default")
      (node (ref "D62") (pin "2") (pinfunction "A_2") (pintype "passive"))
      (node (ref "UP1") (pin "4") (pinfunction "4_4") (pintype "passive"))
    )
    (net (code "50") (name "Net-(D63-A)") (class "Default")
      (node (ref "D63") (pin "2") (pinfunction "A_2") (pintype "passive"))
      (node (ref "DEL1") (pin "4") (pinfunction "4_4") (pintype "passive"))
    )
    (net (code "51") (name "Net-(D64-A)") (class "Default")
      (node (ref "D64") (pin "2") (pinfunction "A_2") (pintype "passive"))
      (node (ref "TAB1") (pin "4") (pinfunction "4_4") (pintype "passive"))
    )
    (net (code "52") (name "Net-(D65-A)") (class "Default")
      (node (ref "A1") (pin "4") (pinfunction "4_4") (pintype "passive"))
      (node (ref "D65") (pin "2") (pinfunction "A_2") (pintype "passive"))
    )
    (net (code "53") (name "Net-(D66-A)") (class "Default")
      (node (ref "D66") (pin "2") (pinfunction "A_2") (pintype "passive"))
      (node (ref "S1") (pin "4") (pinfunction "4_4") (pintype "passive"))
    )
    (net (code "54") (name "Net-(D67-Pad2)") (class "Default")
      (node (ref "D67") (pin "2") (pinfunction "2_2") (pintype "passive"))
      (node (ref "S1") (pin "6") (pinfunction "6_6") (pintype "passive"))
    )
    (net (code "55") (name "Net-(D67-Pad6)") (class "Default")
      (node (ref "D67") (pin "6") (pinfunction "6_6") (pintype "passive"))
      (node (ref "F1") (pin "2") (pinfunction "2_2") (pintype "passive"))
    )
    (net (code "56") (name "Net-(D68-A)") (class "Default")
      (node (ref "D67") (pin "4") (pinfunction "4_4") (pintype "passive"))
      (node (ref "D68") (pin "2") (pinfunction "A_2") (pintype "passive"))
    )
    (net (code "57") (name "Net-(D69-A)") (class "Default")
      (node (ref "D69") (pin "2") (pinfunction "A_2") (pintype "passive"))
      (node (ref "F1") (pin "4") (pinfunction "4_4") (pintype "passive"))
    )
    (net (code "58") (name "Net-(D70-A)") (class "Default")
      (node (ref "D70") (pin "2") (pinfunction "A_2") (pintype "passive"))
      (node (ref "G1") (pin "4") (pinfunction "4_4") (pintype "passive"))
    )
    (net (code "59") (name "Net-(D71-A)") (class "Default")
      (node (ref "D71") (pin "2") (pinfunction "A_2") (pintype "passive"))
      (node (ref "H1") (pin "4") (pinfunction "4_4") (pintype "passive"))
    )
    (net (code "60") (name "Net-(D72-A)") (class "Default")
      (node (ref "D72") (pin "2") (pinfunction "A_2") (pintype "passive"))
      (node (ref "J2") (pin "4") (pinfunction "4_4") (pintype "passive"))
    )
    (net (code "61") (name "Net-(D73-A)") (class "Default")
      (node (ref "D73") (pin "2") (pinfunction "A_2") (pintype "passive"))
      (node (ref "K1") (pin "4") (pinfunction "4_4") (pintype "passive"))
    )
    (net (code "62") (name "Net-(D74-A)") (class "Default")
      (node (ref "D74") (pin "2") (pinfunction "A_2") (pintype "passive"))
      (node (ref "L1") (pin "4") (pinfunction "4_4") (pintype "passive"))
    )
    (net (code "63") (name "Net-(D75-A)") (class "Default")
      (node (ref "D75") (pin "2") (pinfunction "A_2") (pintype "passive"))
      (node (ref "ENTER1") (pin "4") (pinfunction "4_4") (pintype "passive"))
    )
    (net (code "64") (name "Net-(D76-A)") (class "Default")
      (node (ref "BACKSPACE1") (pin "4") (pinfunction "4_4") (pintype "passive"))
      (node (ref "D76") (pin "2") (pinfunction "A_2") (pintype "passive"))
    )
    (net (code "65") (name "Net-(D77-A)") (class "Default")
      (node (ref "D77") (pin "2") (pinfunction "A_2") (pintype "passive"))
      (node (ref "P1") (pin "4") (pinfunction "4_4") (pintype "passive"))
    )
    (net (code "66") (name "Net-(D78-A)") (class "Default")
      (node (ref "D78") (pin "2") (pinfunction "A_2") (pintype "passive"))
      (node (ref "O1") (pin "4") (pinfunction "4_4") (pintype "passive"))
    )
    (net (code "67") (name "Net-(D79-A)") (class "Default")
      (node (ref "D79") (pin "2") (pinfunction "A_2") (pintype "passive"))
      (node (ref "I1") (pin "4") (pinfunction "4_4") (pintype "passive"))
    )
    (net (code "68") (name "Net-(D80-A)") (class "Default")
      (node (ref "D80") (pin "2") (pinfunction "A_2") (pintype "passive"))
      (node (ref "U2") (pin "4") (pinfunction "4_4") (pintype "passive"))
    )
    (net (code "69") (name "Net-(D81-A)") (class "Default")
      (node (ref "D81") (pin "2") (pinfunction "A_2") (pintype "passive"))
      (node (ref "Y1") (pin "4") (pinfunction "4_4") (pintype "passive"))
    )
    (net (code "70") (name "Net-(D82-A)") (class "Default")
      (node (ref "D82") (pin "2") (pinfunction "A_2") (pintype "passive"))
      (node (ref "T1") (pin "4") (pinfunction "4_4") (pintype "passive"))
    )
    (net (code "71") (name "Net-(D83-A)") (class "Default")
      (node (ref "D83") (pin "2") (pinfunction "A_2") (pintype "passive"))
      (node (ref "R6") (pin "4") (pinfunction "4_4") (pintype "passive"))
    )
    (net (code "72") (name "Net-(D84-A)") (class "Default")
      (node (ref "D84") (pin "2") (pinfunction "A_2") (pintype "passive"))
      (node (ref "E1") (pin "4") (pinfunction "4_4") (pintype "passive"))
    )
    (net (code "73") (name "Net-(D85-A)") (class "Default")
      (node (ref "D85") (pin "2") (pinfunction "A_2") (pintype "passive"))
      (node (ref "W1") (pin "4") (pinfunction "4_4") (pintype "passive"))
    )
    (net (code "74") (name "Net-(D86-A)") (class "Default")
      (node (ref "D86") (pin "2") (pinfunction "A_2") (pintype "passive"))
      (node (ref "Q1") (pin "4") (pinfunction "4_4") (pintype "passive"))
    )
    (net (code "75") (name "Net-(D87-A)") (class "Default")
      (node (ref "D87") (pin "2") (pinfunction "A_2") (pintype "passive"))
      (node (ref "ESC1") (pin "4") (pinfunction "4_4") (pintype "passive"))
    )
    (net (code "76") (name "Net-(DEL1-Pad2)") (class "Default")
      (node (ref "DEL1") (pin "2") (pinfunction "2_2") (pintype "passive"))
      (node (ref "UP1") (pin "6") (pinfunction "6_6") (pintype "passive"))
    )
    (net (code "77") (name "Net-(DEL1-Pad6)") (class "Default")
      (node (ref "DEL1") (pin "6") (pinfunction "6_6") (pintype "passive"))
      (node (ref "TAB1") (pin "2") (pinfunction "2_2") (pintype "passive"))
    )
    (net (code "78") (name "Net-(DOWN1-Pad2)") (class "Default")
      (node (ref "DOWN1") (pin "2") (pinfunction "2_2") (pintype "passive"))
      (node (ref "LEFT1") (pin "6") (pinfunction "6_6") (pintype "passive"))
    )
    (net (code "79") (name "Net-(DOWN1-Pad6)") (class "Default")
      (node (ref "DOWN1") (pin "6") (pinfunction "6_6") (pintype "passive"))
      (node (ref "RIGHT1") (pin "2") (pinfunction "2_2") (pintype "passive"))
    )
    (net (code "80") (name "Net-(E1-Pad2)") (class "Default")
      (node (ref "E1") (pin "2") (pinfunction "2_2") (pintype "passive"))
      (node (ref "W1") (pin "6") (pinfunction "6_6") (pintype "passive"))
    )
    (net (code "81") (name "Net-(E1-Pad6)") (class "Default")
      (node (ref "E1") (pin "6") (pinfunction "6_6") (pintype "passive"))
      (node (ref "R6") (pin "2") (pinfunction "2_2") (pintype "passive"))
    )
    (net (code "82") (name "Net-(ENTER1-Pad2)") (class "Default")
      (node (ref "ENTER1") (pin "2") (pinfunction "2_2") (pintype "passive"))
      (node (ref "L1") (pin "6") (pinfunction "6_6") (pintype "passive"))
    )
    (net (code "83") (name "Net-(ENTER1-Pad6)") (class "Default")
      (node (ref "ENTER1") (pin "6") (pinfunction "6_6") (pintype "passive"))
      (node (ref "ESC1") (pin "2") (pinfunction "2_2") (pintype "passive"))
    )
    (net (code "84") (name "Net-(ESC1-Pad6)") (class "Default")
      (node (ref "ESC1") (pin "6") (pinfunction "6_6") (pintype "passive"))
      (node (ref "Q1") (pin "2") (pinfunction "2_2") (pintype "passive"))
    )
    (net (code "85") (name "Net-(F1-Pad6)") (class "Default")
      (node (ref "F1") (pin "6") (pinfunction "6_6") (pintype "passive"))
      (node (ref "G1") (pin "2") (pinfunction "2_2") (pintype "passive"))
    )
    (net (code "86") (name "Net-(G1-Pad6)") (class "Default")
      (node (ref "G1") (pin "6") (pinfunction "6_6") (pintype "passive"))
      (node (ref "H1") (pin "2") (pinfunction "2_2") (pintype "passive"))
    )
    (net (code "87") (name "Net-(H1-Pad6)") (class "Default")
      (node (ref "H1") (pin "6") (pinfunction "6_6") (pintype "passive"))
      (node (ref "J2") (pin "2") (pinfunction "2_2") (pintype "passive"))
    )
    (net (code "88") (name "Net-(I1-Pad2)") (class "Default")
      (node (ref "I1") (pin "2") (pinfunction "2_2") (pintype "passive"))
      (node (ref "U2") (pin "6") (pinfunction "6_6") (pintype "passive"))
    )
    (net (code "89") (name "Net-(I1-Pad6)") (class "Default")
      (node (ref "I1") (pin "6") (pinfunction "6_6") (pintype "passive"))
      (node (ref "O1") (pin "2") (pinfunction "2_2") (pintype "passive"))
    )
    (net (code "90") (name "Net-(J2-Pad6)") (class "Default")
      (node (ref "J2") (pin "6") (pinfunction "6_6") (pintype "passive"))
      (node (ref "K1") (pin "2") (pinfunction "2_2") (pintype "passive"))
    )
    (net (code "91") (name "Net-(J3-Pad2)") (class "Default")
      (node (ref "J3") (pin "2") (pinfunction "2_2") (pintype "passive"))
      (node (ref "LCTRL1") (pin "2") (pinfunction "2_2") (pintype "passive"))
    )
    (net (code "92") (name "Net-(K1-Pad6)") (class "Default")
      (node (ref "K1") (pin "6") (pinfunction "6_6") (pintype "passive"))
      (node (ref "L1") (pin "2") (pinfunction "2_2") (pintype "passive"))
    )
    (net (code "93") (name "Net-(LALT1-Pad2)") (class "Default")
      (node (ref "LALT1") (pin "2") (pinfunction "2_2") (pintype "passive"))
      (node (ref "LGUI1") (pin "6") (pinfunction "6_6") (pintype "passive"))
    )
    (net (code "94") (name "Net-(LALT1-Pad6)") (class "Default")
      (node (ref "LALT1") (pin "6") (pinfunction "6_6") (pintype "passive"))
      (node (ref "SPACE1") (pin "2") (pinfunction "2_2") (pintype "passive"))
    )
    (net (code "95") (name "Net-(LCTRL1-Pad6)") (class "Default")
      (node (ref "LCTRL1") (pin "6") (pinfunction "6_6") (pintype "passive"))
      (node (ref "LGUI1") (pin "2") (pinfunction "2_2") (pintype "passive"))
    )
    (net (code "96") (name "Net-(LED1-K)") (class "Default")
      (node (ref "LED1") (pin "2") (pinfunction "K_2") (pintype "passive"))
      (node (ref "R7") (pin "2") (pinfunction "2_2") (pintype "passive"))
    )
    (net (code "97") (name "Net-(LSHIFT1-Pad2)") (class "Default")
      (node (ref "LSHIFT1") (pin "2") (pinfunction "2_2") (pintype "passive"))
      (node (ref "RIGHT1") (pin "6") (pinfunction "6_6") (pintype "passive"))
    )
    (net (code "98") (name "Net-(LSHIFT1-Pad6)") (class "Default")
      (node (ref "LSHIFT1") (pin "6") (pinfunction "6_6") (pintype "passive"))
      (node (ref "Z1") (pin "2") (pinfunction "2_2") (pintype "passive"))
    )
    (net (code "99") (name "Net-(M1-Pad2)") (class "Default")
      (node (ref "M1") (pin "2") (pinfunction "2_2") (pintype "passive"))
      (node (ref "N1") (pin "6") (pinfunction "6_6") (pintype "passive"))
    )
    (net (code "100") (name "Net-(M1-Pad6)") (class "Default")
      (node (ref "M1") (pin "6") (pinfunction "6_6") (pintype "passive"))
      (node (ref "TO1") (pin "2") (pinfunction "2_2") (pintype "passive"))
    )
    (net (code "101") (name "Net-(O1-Pad6)") (class "Default")
      (node (ref "O1") (pin "6") (pinfunction "6_6") (pintype "passive"))
      (node (ref "P1") (pin "2") (pinfunction "2_2") (pintype "passive"))
    )
    (net (code "102") (name "Net-(Q1-Pad6)") (class "Default")
      (node (ref "Q1") (pin "6") (pinfunction "6_6") (pintype "passive"))
      (node (ref "W1") (pin "2") (pinfunction "2_2") (pintype "passive"))
    )
    (net (code "103") (name "Net-(R6-Pad6)") (class "Default")
      (node (ref "R6") (pin "6") (pinfunction "6_6") (pintype "passive"))
      (node (ref "T1") (pin "2") (pinfunction "2_2") (pintype "passive"))
    )
    (net (code "104") (name "Net-(RSHIFT1-Pad2)") (class "Default")
      (node (ref "RSHIFT1") (pin "2") (pinfunction "2_2") (pintype "passive"))
      (node (ref "SPACE1") (pin "6") (pinfunction "6_6") (pintype "passive"))
    )
    (net (code "105") (name "Net-(T1-Pad6)") (class "Default")
      (node (ref "T1") (pin "6") (pinfunction "6_6") (pintype "passive"))
      (node (ref "Y1") (pin "2") (pinfunction "2_2") (pintype "passive"))
    )
    (net (code "106") (name "Net-(TO1-Pad6)") (class "Default")
      (node (ref "TO1") (pin "6") (pinfunction "6_6") (pintype "passive"))
      (node (ref "UP1") (pin "2") (pinfunction "2_2") (pintype "passive"))
    )
    (net (code "107") (name "Net-(U2-Pad2)") (class "Default")
      (node (ref "U2") (pin "2") (pinfunction "2_2") (pintype "passive"))
      (node (ref "Y1") (pin "6") (pinfunction "6_6") (pintype "passive"))
    )
    (net (code "108") (name "Net-(X2-Pad2)") (class "Default")
      (node (ref "X2") (pin "2") (pinfunction "2_2") (pintype "passive"))
      (node (ref "Z1") (pin "6") (pinfunction "6_6") (pintype "passive"))
    )
    (net (code "109") (name "VBUS") (class "Default")
      (node (ref "USBC2") (pin "A4") (pinfunction "VBUS_A4") (pintype "passive"))
      (node (ref "USBC2") (pin "A9") (pinfunction "VBUS_A9") (pintype "passive"))
      (node (ref "USBC2") (pin "B4") (pinfunction "VBUS_B4") (pintype "passive"))
      (node (ref "USBC2") (pin "B9") (pinfunction "VBUS_B9") (pintype "passive"))
    )
    (net (code "110") (name "VCC") (class "Default")
      (node (ref "A1") (pin "1") (pinfunction "1_1") (pintype "passive"))
      (node (ref "B1") (pin "1") (pinfunction "1_1") (pintype "passive"))
      (node (ref "BACKSPACE1") (pin "1") (pinfunction "1_1") (pintype "passive"))
      (node (ref "C9") (pin "1") (pinfunction "1_1") (pintype "passive"))
      (node (ref "CAPS1") (pin "1") (pinfunction "1_1") (pintype "passive"))
      (node (ref "D67") (pin "1") (pinfunction "1_1") (pintype "passive"))
      (node (ref "DEL1") (pin "1") (pinfunction "1_1") (pintype "passive"))
      (node (ref "DOWN1") (pin "1") (pinfunction "1_1") (pintype "passive"))
      (node (ref "E1") (pin "1") (pinfunction "1_1") (pintype "passive"))
      (node (ref "ENTER1") (pin "1") (pinfunction "1_1") (pintype "passive"))
      (node (ref "ESC1") (pin "1") (pinfunction "1_1") (pintype "passive"))
      (node (ref "F1") (pin "1") (pinfunction "1_1") (pintype "passive"))
      (node (ref "G1") (pin "1") (pinfunction "1_1") (pintype "passive"))
      (node (ref "H1") (pin "1") (pinfunction "1_1") (pintype "passive"))
      (node (ref "I1") (pin "1") (pinfunction "1_1") (pintype "passive"))
      (node (ref "J2") (pin "1") (pinfunction "1_1") (pintype "passive"))
      (node (ref "J3") (pin "3") (pinfunction "3_3") (pintype "passive"))
      (node (ref "K1") (pin "1") (pinfunction "1_1") (pintype "passive"))
      (node (ref "L1") (pin "1") (pinfunction "1_1") (pintype "passive"))
      (node (ref "LALT1") (pin "1") (pinfunction "1_1") (pintype "passive"))
      (node (ref "LCTRL1") (pin "1") (pinfunction "1_1") (pintype "passive"))
      (node (ref "LED1") (pin "1") (pinfunction "A_1") (pintype "passive"))
      (node (ref "LEFT1") (pin "1") (pinfunction "1_1") (pintype "passive"))
      (node (ref "LGUI1") (pin "1") (pinfunction "1_1") (pintype "passive"))
      (node (ref "LSHIFT1") (pin "1") (pinfunction "1_1") (pintype "passive"))
      (node (ref "M1") (pin "1") (pinfunction "1_1") (pintype "passive"))
      (node (ref "N1") (pin "1") (pinfunction "1_1") (pintype "passive"))
      (node (ref "O1") (pin "1") (pinfunction "1_1") (pintype "passive"))
      (node (ref "P1") (pin "1") (pinfunction "1_1") (pintype "passive"))
      (node (ref "Q1") (pin "1") (pinfunction "1_1") (pintype "passive"))
      (node (ref "R6") (pin "1") (pinfunction "1_1") (pintype "passive"))
      (node (ref "RIGHT1") (pin "1") (pinfunction "1_1") (pintype "passive"))
      (node (ref "RSHIFT1") (pin "1") (pinfunction "1_1") (pintype "passive"))
      (node (ref "S1") (pin "1") (pinfunction "1_1") (pintype "passive"))
      (node (ref "SPACE1") (pin "1") (pinfunction "1_1") (pintype "passive"))
      (node (ref "T1") (pin "1") (pinfunction "1_1") (pintype "passive"))
      (node (ref "TAB1") (pin "1") (pinfunction "1_1") (pintype "passive"))
      (node (ref "TO1") (pin "1") (pinfunction "1_1") (pintype "passive"))
      (node (ref "U2") (pin "1") (pinfunction "1_1") (pintype "passive"))
      (node (ref "U5") (pin "5") (pinfunction "5_5") (pintype "passive"))
      (node (ref "U6") (pin "4") (pinfunction "4_4") (pintype "passive"))
      (node (ref "UP1") (pin "1") (pinfunction "1_1") (pintype "passive"))
      (node (ref "V1") (pin "1") (pinfunction "1_1") (pintype "passive"))
      (node (ref "W1") (pin "1") (pinfunction "1_1") (pintype "passive"))
      (node (ref "X2") (pin "1") (pinfunction "1_1") (pintype "passive"))
      (node (ref "Y1") (pin "1") (pinfunction "1_1") (pintype "passive"))
      (node (ref "Z1") (pin "1") (pinfunction "1_1") (pintype "passive"))
    )
    (net (code "111") (name "unconnected-(USBC2-CC1-PadA5)") (class "Default")
      (node (ref "USBC2") (pin "A5") (pinfunction "CC1_A5") (pintype "passive+no_connect"))
    )
    (net (code "112") (name "unconnected-(USBC2-CC2-PadB5)") (class "Default")
      (node (ref "USBC2") (pin "B5") (pinfunction "CC2_B5") (pintype "passive+no_connect"))
    )
    (net (code "113") (name "unconnected-(USBC2-SBU1-PadA8)") (class "Default")
      (node (ref "USBC2") (pin "A8") (pinfunction "SBU1_A8") (pintype "passive+no_connect"))
    )
    (net (code "114") (name "unconnected-(USBC2-SBU2-PadB8)") (class "Default")
      (node (ref "USBC2") (pin "B8") (pinfunction "SBU2_B8") (pintype "passive+no_connect"))
    )
  )
)
